# ESP32.net
KiCad netlist of a schematic drawn in Altium Designer
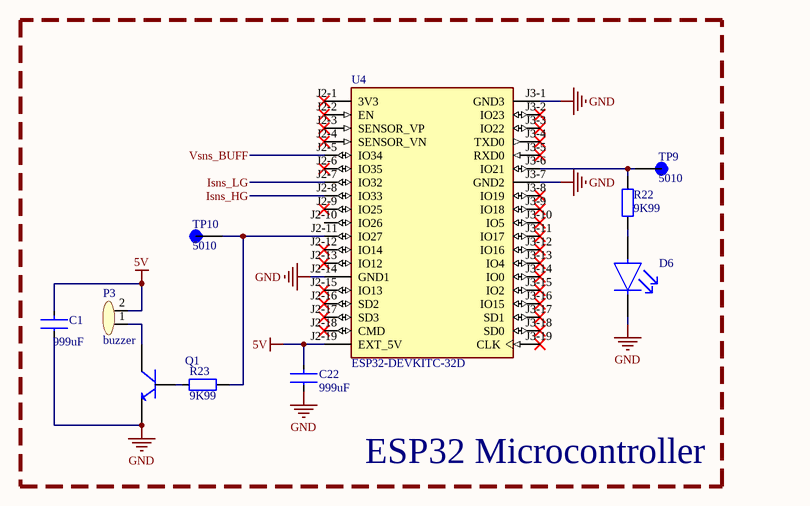
[diagram p0: ESP32.SchDoc]

(export (version "E")
  (design (tool "Eeschema 10.0.6"))
  (components
    (comp (ref "C1")
      (value "CL21B104KBCNNNC")
      (footprint "FP-CL21-IPC_A")
      (description "0805 Cap General Purpose")
      (fields
        (field (name "TOLERANCE") "10%")
        (field (name "VOLTAGE") "50V")
        (field (name "CAPACITANCE") "999uF")
      )
      (libsource (lib "Capstone_intlib") (part "0805CAP"))
    )
    (comp (ref "C22")
      (value "CL21B104KBCNNNC")
      (footprint "FP-CL21-IPC_A")
      (description "0805 Cap General Purpose")
      (fields
        (field (name "TOLERANCE") "10%")
        (field (name "VOLTAGE") "50V")
        (field (name "CAPACITANCE") "999uF")
      )
      (libsource (lib "Capstone_intlib") (part "0805CAP"))
    )
    (comp (ref "D6")
      (value "LTST-C170GKT")
      (footprint "FP-LTST-C170GKT-MFG")
      (description "LED yellow green 0805 wavelength 569nm light intensity 6mcd Front Mounting")
      (fields (field (name "VOLTAGE") "5V") (field (name "MANUFACTURER") "Lite-On"))
      (libsource (lib "Capstone_intlib") (part "CMP-1674-00002-6"))
    )
    (comp (ref "P3")
      (value "buzzer")
      (footprint "ece-buzzer")
      (libsource (lib "ece components") (part "buzzer"))
    )
    (comp (ref "Q1")
      (value "BC547/549")
      (footprint "ece-TO-92Z")
      (description "NPN Transistor")
      (libsource (lib "ece components") (part "BC547/549"))
    )
    (comp (ref "R22")
      (value "RC0805FR-071KL")
      (footprint "RESC2013X60X35ML10T20")
      (description "0805 General Purpose  0.125W SMD")
      (fields
        (field (name "TOLERANCE") "1%")
        (field (name "MANUFACTURER") "Yageo")
        (field (name "RESISTANCE") "9K99")
      )
      (libsource (lib "Capstone_intlib") (part "0805RESISTOR"))
    )
    (comp (ref "R23")
      (value "RC0805FR-071KL")
      (footprint "RESC2013X60X35ML10T20")
      (description "0805 General Purpose  0.125W SMD")
      (fields
        (field (name "TOLERANCE") "1%")
        (field (name "MANUFACTURER") "Yageo")
        (field (name "RESISTANCE") "9K99")
      )
      (libsource (lib "") (part "0805RESISTOR_1"))
    )
    (comp (ref "TP9")
      (value "5010")
      (footprint "TP_5010")
      (description "Test Point MultiPurpose THM .445 L .125 OD Heat Resistant Nylon 46 Red ¦ Keystone Electronics 5010")
      (fields (field (name "MF") "Keystone Electronics"))
      (libsource (lib "5010") (part "5010"))
    )
    (comp (ref "TP10")
      (value "5010")
      (footprint "TP_5010")
      (description "Test Point MultiPurpose THM .445 L .125 OD Heat Resistant Nylon 46 Red ¦ Keystone Electronics 5010")
      (fields (field (name "MF") "Keystone Electronics"))
      (libsource (lib "5010") (part "5010"))
    )
    (comp (ref "U4")
      (value "ESP32-DEVKITC-32D")
      (footprint "MODULE_ESP32-DEVKITC-32D")
      (description "WiFi Development Tools (802.11) ESP32 General Development Kit, ESP32-WROOM-32D on the board")
      (fields (field (name "MF") "Espressif Systems"))
      (libsource (lib "ESP32-DEVKITC-32D (1)") (part "ESP32-DEVKITC-32D"))
    )
  )
  (nets
    (net (code "1") (name "/Isns_HG") (class "Default")
      (node (ref "U4") (pin "J2-8") (pinfunction "IO33_J2-8") (pintype "bidirectional"))
    )
    (net (code "2") (name "/Isns_LG") (class "Default")
      (node (ref "U4") (pin "J2-7") (pinfunction "IO32_J2-7") (pintype "bidirectional"))
    )
    (net (code "3") (name "/Vsns_BUFF") (class "Default")
      (node (ref "U4") (pin "J2-5") (pinfunction "IO34_J2-5") (pintype "bidirectional"))
    )
    (net (code "4") (name "5V") (class "Default")
      (node (ref "C1") (pin "1") (pinfunction "1_1") (pintype "passive"))
      (node (ref "C22") (pin "1") (pinfunction "1_1") (pintype "passive"))
      (node (ref "P3") (pin "2") (pinfunction "2_2") (pintype "passive"))
      (node (ref "U4") (pin "J2-19") (pinfunction "EXT_5V_J2-19") (pintype "power_in"))
    )
    (net (code "5") (name "GND") (class "Default")
      (node (ref "C1") (pin "2") (pinfunction "2_2") (pintype "passive"))
      (node (ref "C22") (pin "2") (pinfunction "2_2") (pintype "passive"))
      (node (ref "D6") (pin "1") (pinfunction "C_1") (pintype "passive"))
      (node (ref "Q1") (pin "3") (pinfunction "E_3") (pintype "passive"))
      (node (ref "U4") (pin "J2-14") (pinfunction "GND1_J2-14") (pintype "power_in"))
      (node (ref "U4") (pin "J3-1") (pinfunction "GND3_J3-1") (pintype "power_in"))
      (node (ref "U4") (pin "J3-7") (pinfunction "GND2_J3-7") (pintype "power_in"))
    )
    (net (code "6") (name "Net-(D6-A)") (class "Default")
      (node (ref "D6") (pin "2") (pinfunction "A_2") (pintype "passive"))
      (node (ref "R22") (pin "1") (pinfunction "1_1") (pintype "passive"))
    )
    (net (code "7") (name "Net-(Q1-B)") (class "Default")
      (node (ref "Q1") (pin "2") (pinfunction "B_2") (pintype "passive"))
      (node (ref "R23") (pin "2") (pinfunction "2_2") (pintype "passive"))
    )
    (net (code "8") (name "Net-(Q1-C)") (class "Default")
      (node (ref "P3") (pin "1") (pinfunction "1_1") (pintype "passive"))
      (node (ref "Q1") (pin "1") (pinfunction "C_1") (pintype "passive"))
    )
    (net (code "9") (name "Net-(U4-IO21)") (class "Default")
      (node (ref "R22") (pin "2") (pinfunction "2_2") (pintype "passive"))
      (node (ref "TP9") (pin "TP") (pinfunction "TP_TP") (pintype "passive"))
      (node (ref "U4") (pin "J3-6") (pinfunction "IO21_J3-6") (pintype "bidirectional"))
    )
    (net (code "10") (name "Net-(U4-IO27)") (class "Default")
      (node (ref "R23") (pin "1") (pinfunction "1_1") (pintype "passive"))
      (node (ref "TP10") (pin "TP") (pinfunction "TP_TP") (pintype "passive"))
      (node (ref "U4") (pin "J2-11") (pinfunction "IO27_J2-11") (pintype "bidirectional"))
    )
    (net (code "11") (name "unconnected-(U4-3V3-PadJ2-1)") (class "Default")
      (node (ref "U4") (pin "J2-1") (pinfunction "3V3_J2-1") (pintype "power_in+no_connect"))
    )
    (net (code "12") (name "unconnected-(U4-CLK-PadJ3-19)") (class "Default")
      (node (ref "U4") (pin "J3-19") (pinfunction "CLK_J3-19") (pintype "input+no_connect"))
    )
    (net (code "13") (name "unconnected-(U4-CMD-PadJ2-18)") (class "Default")
      (node (ref "U4") (pin "J2-18") (pinfunction "CMD_J2-18") (pintype "bidirectional+no_connect"))
    )
    (net (code "14") (name "unconnected-(U4-EN-PadJ2-2)") (class "Default")
      (node (ref "U4") (pin "J2-2") (pinfunction "EN_J2-2") (pintype "input+no_connect"))
    )
    (net (code "15") (name "unconnected-(U4-IO0-PadJ3-14)") (class "Default")
      (node (ref "U4") (pin "J3-14") (pinfunction "IO0_J3-14") (pintype "bidirectional+no_connect"))
    )
    (net (code "16") (name "unconnected-(U4-IO2-PadJ3-15)") (class "Default")
      (node (ref "U4") (pin "J3-15") (pinfunction "IO2_J3-15") (pintype "bidirectional+no_connect"))
    )
    (net (code "17") (name "unconnected-(U4-IO4-PadJ3-13)") (class "Default")
      (node (ref "U4") (pin "J3-13") (pinfunction "IO4_J3-13") (pintype "bidirectional+no_connect"))
    )
    (net (code "18") (name "unconnected-(U4-IO5-PadJ3-10)") (class "Default")
      (node (ref "U4") (pin "J3-10") (pinfunction "IO5_J3-10") (pintype "bidirectional+no_connect"))
    )
    (net (code "19") (name "unconnected-(U4-IO12-PadJ2-13)") (class "Default")
      (node (ref "U4") (pin "J2-13") (pinfunction "IO12_J2-13") (pintype "bidirectional+no_connect"))
    )
    (net (code "20") (name "unconnected-(U4-IO13-PadJ2-15)") (class "Default")
      (node (ref "U4") (pin "J2-15") (pinfunction "IO13_J2-15") (pintype "bidirectional+no_connect"))
    )
    (net (code "21") (name "unconnected-(U4-IO14-PadJ2-12)") (class "Default")
      (node (ref "U4") (pin "J2-12") (pinfunction "IO14_J2-12") (pintype "bidirectional+no_connect"))
    )
    (net (code "22") (name "unconnected-(U4-IO15-PadJ3-16)") (class "Default")
      (node (ref "U4") (pin "J3-16") (pinfunction "IO15_J3-16") (pintype "bidirectional+no_connect"))
    )
    (net (code "23") (name "unconnected-(U4-IO16-PadJ3-12)") (class "Default")
      (node (ref "U4") (pin "J3-12") (pinfunction "IO16_J3-12") (pintype "bidirectional+no_connect"))
    )
    (net (code "24") (name "unconnected-(U4-IO17-PadJ3-11)") (class "Default")
      (node (ref "U4") (pin "J3-11") (pinfunction "IO17_J3-11") (pintype "bidirectional+no_connect"))
    )
    (net (code "25") (name "unconnected-(U4-IO18-PadJ3-9)") (class "Default")
      (node (ref "U4") (pin "J3-9") (pinfunction "IO18_J3-9") (pintype "bidirectional+no_connect"))
    )
    (net (code "26") (name "unconnected-(U4-IO19-PadJ3-8)") (class "Default")
      (node (ref "U4") (pin "J3-8") (pinfunction "IO19_J3-8") (pintype "bidirectional+no_connect"))
    )
    (net (code "27") (name "unconnected-(U4-IO22-PadJ3-3)") (class "Default")
      (node (ref "U4") (pin "J3-3") (pinfunction "IO22_J3-3") (pintype "bidirectional+no_connect"))
    )
    (net (code "28") (name "unconnected-(U4-IO23-PadJ3-2)") (class "Default")
      (node (ref "U4") (pin "J3-2") (pinfunction "IO23_J3-2") (pintype "bidirectional+no_connect"))
    )
    (net (code "29") (name "unconnected-(U4-IO25-PadJ2-9)") (class "Default")
      (node (ref "U4") (pin "J2-9") (pinfunction "IO25_J2-9") (pintype "bidirectional+no_connect"))
    )
    (net (code "30") (name "unconnected-(U4-IO26-PadJ2-10)") (class "Default")
      (node (ref "U4") (pin "J2-10") (pinfunction "IO26_J2-10") (pintype "bidirectional"))
    )
    (net (code "31") (name "unconnected-(U4-IO35-PadJ2-6)") (class "Default")
      (node (ref "U4") (pin "J2-6") (pinfunction "IO35_J2-6") (pintype "bidirectional+no_connect"))
    )
    (net (code "32") (name "unconnected-(U4-RXD0-PadJ3-5)") (class "Default")
      (node (ref "U4") (pin "J3-5") (pinfunction "RXD0_J3-5") (pintype "input+no_connect"))
    )
    (net (code "33") (name "unconnected-(U4-SD0-PadJ3-18)") (class "Default")
      (node (ref "U4") (pin "J3-18") (pinfunction "SD0_J3-18") (pintype "bidirectional+no_connect"))
    )
    (net (code "34") (name "unconnected-(U4-SD1-PadJ3-17)") (class "Default")
      (node (ref "U4") (pin "J3-17") (pinfunction "SD1_J3-17") (pintype "bidirectional+no_connect"))
    )
    (net (code "35") (name "unconnected-(U4-SD2-PadJ2-16)") (class "Default")
      (node (ref "U4") (pin "J2-16") (pinfunction "SD2_J2-16") (pintype "bidirectional+no_connect"))
    )
    (net (code "36") (name "unconnected-(U4-SD3-PadJ2-17)") (class "Default")
      (node (ref "U4") (pin "J2-17") (pinfunction "SD3_J2-17") (pintype "bidirectional+no_connect"))
    )
    (net (code "37") (name "unconnected-(U4-SENSOR_VN-PadJ2-4)") (class "Default")
      (node (ref "U4") (pin "J2-4") (pinfunction "SENSOR_VN_J2-4") (pintype "input+no_connect"))
    )
    (net (code "38") (name "unconnected-(U4-SENSOR_VP-PadJ2-3)") (class "Default")
      (node (ref "U4") (pin "J2-3") (pinfunction "SENSOR_VP_J2-3") (pintype "input+no_connect"))
    )
    (net (code "39") (name "unconnected-(U4-TXD0-PadJ3-4)") (class "Default")
      (node (ref "U4") (pin "J3-4") (pinfunction "TXD0_J3-4") (pintype "output+no_connect"))
    )
  )
)
